# DAC_PCM1781.net
KiCad netlist of a schematic drawn in Altium Designer
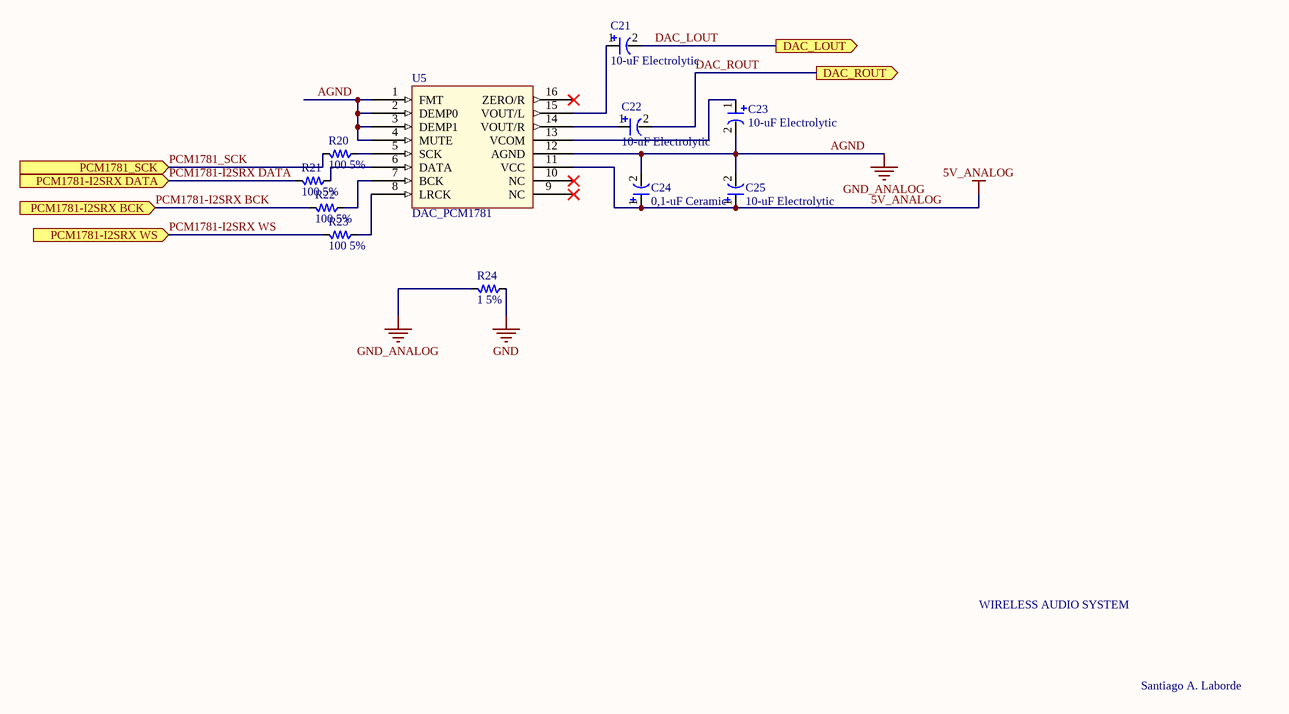
[diagram p0: DAC_PCM1781.SchDoc]

(export (version "E")
  (design (tool "Eeschema 10.0.6"))
  (components
    (comp (ref "C21")
      (value "10-uF Electrolytic")
      (footprint "14-1210")
      (description "Polarysed Capacitor")
      (libsource (lib "TD2_Project") (part "Capacitor_Pol"))
    )
    (comp (ref "C22")
      (value "10-uF Electrolytic")
      (footprint "14-1210")
      (description "Polarysed Capacitor")
      (libsource (lib "TD2_Project") (part "Capacitor_Pol"))
    )
    (comp (ref "C23")
      (value "10-uF Electrolytic")
      (footprint "14-1210")
      (description "Polarysed Capacitor")
      (libsource (lib "TD2_Project") (part "Capacitor_Pol"))
    )
    (comp (ref "C24")
      (value "0,1-uF Ceramic")
      (footprint "C_0805_Pol")
      (description "Polarysed Capacitor")
      (libsource (lib "TD2_Project") (part "Capacitor_Pol"))
    )
    (comp (ref "C25")
      (value "10-uF Electrolytic")
      (footprint "14-1210")
      (description "Polarysed Capacitor")
      (libsource (lib "TD2_Project") (part "Capacitor_Pol"))
    )
    (comp (ref "R20") (value "100 5%") (footprint "R_0805") (libsource (lib "TD2_Project") (part "Resistor")))
    (comp (ref "R21") (value "100 5%") (footprint "R_0805") (libsource (lib "TD2_Project") (part "Resistor")))
    (comp (ref "R22") (value "100 5%") (footprint "R_0805") (libsource (lib "TD2_Project") (part "Resistor")))
    (comp (ref "R23") (value "100 5%") (footprint "R_0805") (libsource (lib "TD2_Project") (part "Resistor")))
    (comp (ref "R24") (value "1 5%") (footprint "R_0805") (libsource (lib "TD2_Project") (part "Resistor")))
    (comp (ref "U5")
      (value "DAC_PCM1781")
      (footprint "SSOP (16)")
      (libsource (lib "TD2_Project") (part "DAC_PCM1781"))
    )
  )
  (nets
    (net (code "1") (name "/DAC_LOUT") (class "Default") (node (ref "C21") (pin "2") (pintype "passive")))
    (net (code "2") (name "/DAC_ROUT") (class "Default") (node (ref "C22") (pin "2") (pintype "passive")))
    (net (code "3") (name "/PCM1781-I2SRX BCK") (class "Default")
      (node (ref "R22") (pin "1") (pinfunction "1_1") (pintype "passive"))
    )
    (net (code "4") (name "/PCM1781-I2SRX DATA") (class "Default")
      (node (ref "R21") (pin "1") (pinfunction "1_1") (pintype "passive"))
    )
    (net (code "5") (name "/PCM1781-I2SRX WS") (class "Default")
      (node (ref "R23") (pin "1") (pinfunction "1_1") (pintype "passive"))
    )
    (net (code "6") (name "/PCM1781_SCK") (class "Default")
      (node (ref "R20") (pin "1") (pinfunction "1_1") (pintype "passive"))
    )
    (net (code "7") (name "5V_ANALOG") (class "Default")
      (node (ref "C24") (pin "1") (pintype "passive"))
      (node (ref "C25") (pin "1") (pintype "passive"))
      (node (ref "U5") (pin "11") (pinfunction "VCC_11") (pintype "passive"))
    )
    (net (code "8") (name "GND") (class "Default")
      (node (ref "R24") (pin "2") (pinfunction "2_2") (pintype "passive"))
    )
    (net (code "9") (name "GND_ANALOG") (class "Default")
      (node (ref "C23") (pin "2") (pintype "passive"))
      (node (ref "C24") (pin "2") (pintype "passive"))
      (node (ref "C25") (pin "2") (pintype "passive"))
      (node (ref "R24") (pin "1") (pinfunction "1_1") (pintype "passive"))
      (node (ref "U5") (pin "1") (pinfunction "FMT_1") (pintype "input"))
      (node (ref "U5") (pin "12") (pinfunction "AGND_12") (pintype "passive"))
      (node (ref "U5") (pin "2") (pinfunction "DEMP0_2") (pintype "input"))
      (node (ref "U5") (pin "3") (pinfunction "DEMP1_3") (pintype "input"))
      (node (ref "U5") (pin "4") (pinfunction "MUTE_4") (pintype "input"))
    )
    (net (code "10") (name "Net-(U5-BCK)") (class "Default")
      (node (ref "R22") (pin "2") (pinfunction "2_2") (pintype "passive"))
      (node (ref "U5") (pin "7") (pinfunction "BCK_7") (pintype "input"))
    )
    (net (code "11") (name "Net-(U5-DATA)") (class "Default")
      (node (ref "R21") (pin "2") (pinfunction "2_2") (pintype "passive"))
      (node (ref "U5") (pin "6") (pinfunction "DATA_6") (pintype "input"))
    )
    (net (code "12") (name "Net-(U5-LRCK)") (class "Default")
      (node (ref "R23") (pin "2") (pinfunction "2_2") (pintype "passive"))
      (node (ref "U5") (pin "8") (pinfunction "LRCK_8") (pintype "input"))
    )
    (net (code "13") (name "Net-(U5-SCK)") (class "Default")
      (node (ref "R20") (pin "2") (pinfunction "2_2") (pintype "passive"))
      (node (ref "U5") (pin "5") (pinfunction "SCK_5") (pintype "input"))
    )
    (net (code "14") (name "Net-(U5-VCOM)") (class "Default")
      (node (ref "C23") (pin "1") (pintype "passive"))
      (node (ref "U5") (pin "13") (pinfunction "VCOM_13") (pintype "passive"))
    )
    (net (code "15") (name "Net-(U5-VOUT{slash}L)") (class "Default")
      (node (ref "C21") (pin "1") (pintype "passive"))
      (node (ref "U5") (pin "15") (pinfunction "VOUT/L_15") (pintype "output"))
    )
    (net (code "16") (name "Net-(U5-VOUT{slash}R)") (class "Default")
      (node (ref "C22") (pin "1") (pintype "passive"))
      (node (ref "U5") (pin "14") (pinfunction "VOUT/R_14") (pintype "output"))
    )
    (net (code "17") (name "unconnected-(U5-NC-Pad9)") (class "Default")
      (node (ref "U5") (pin "9") (pinfunction "NC_9") (pintype "passive+no_connect"))
    )
    (net (code "18") (name "unconnected-(U5-NC-Pad10)") (class "Default")
      (node (ref "U5") (pin "10") (pinfunction "NC_10") (pintype "passive+no_connect"))
    )
    (net (code "19") (name "unconnected-(U5-ZERO{slash}R-Pad16)") (class "Default")
      (node (ref "U5") (pin "16") (pinfunction "ZERO/R_16") (pintype "output+no_connect"))
    )
  )
)
